# EthernetPHY.net
KiCad netlist of a schematic drawn in Altium Designer
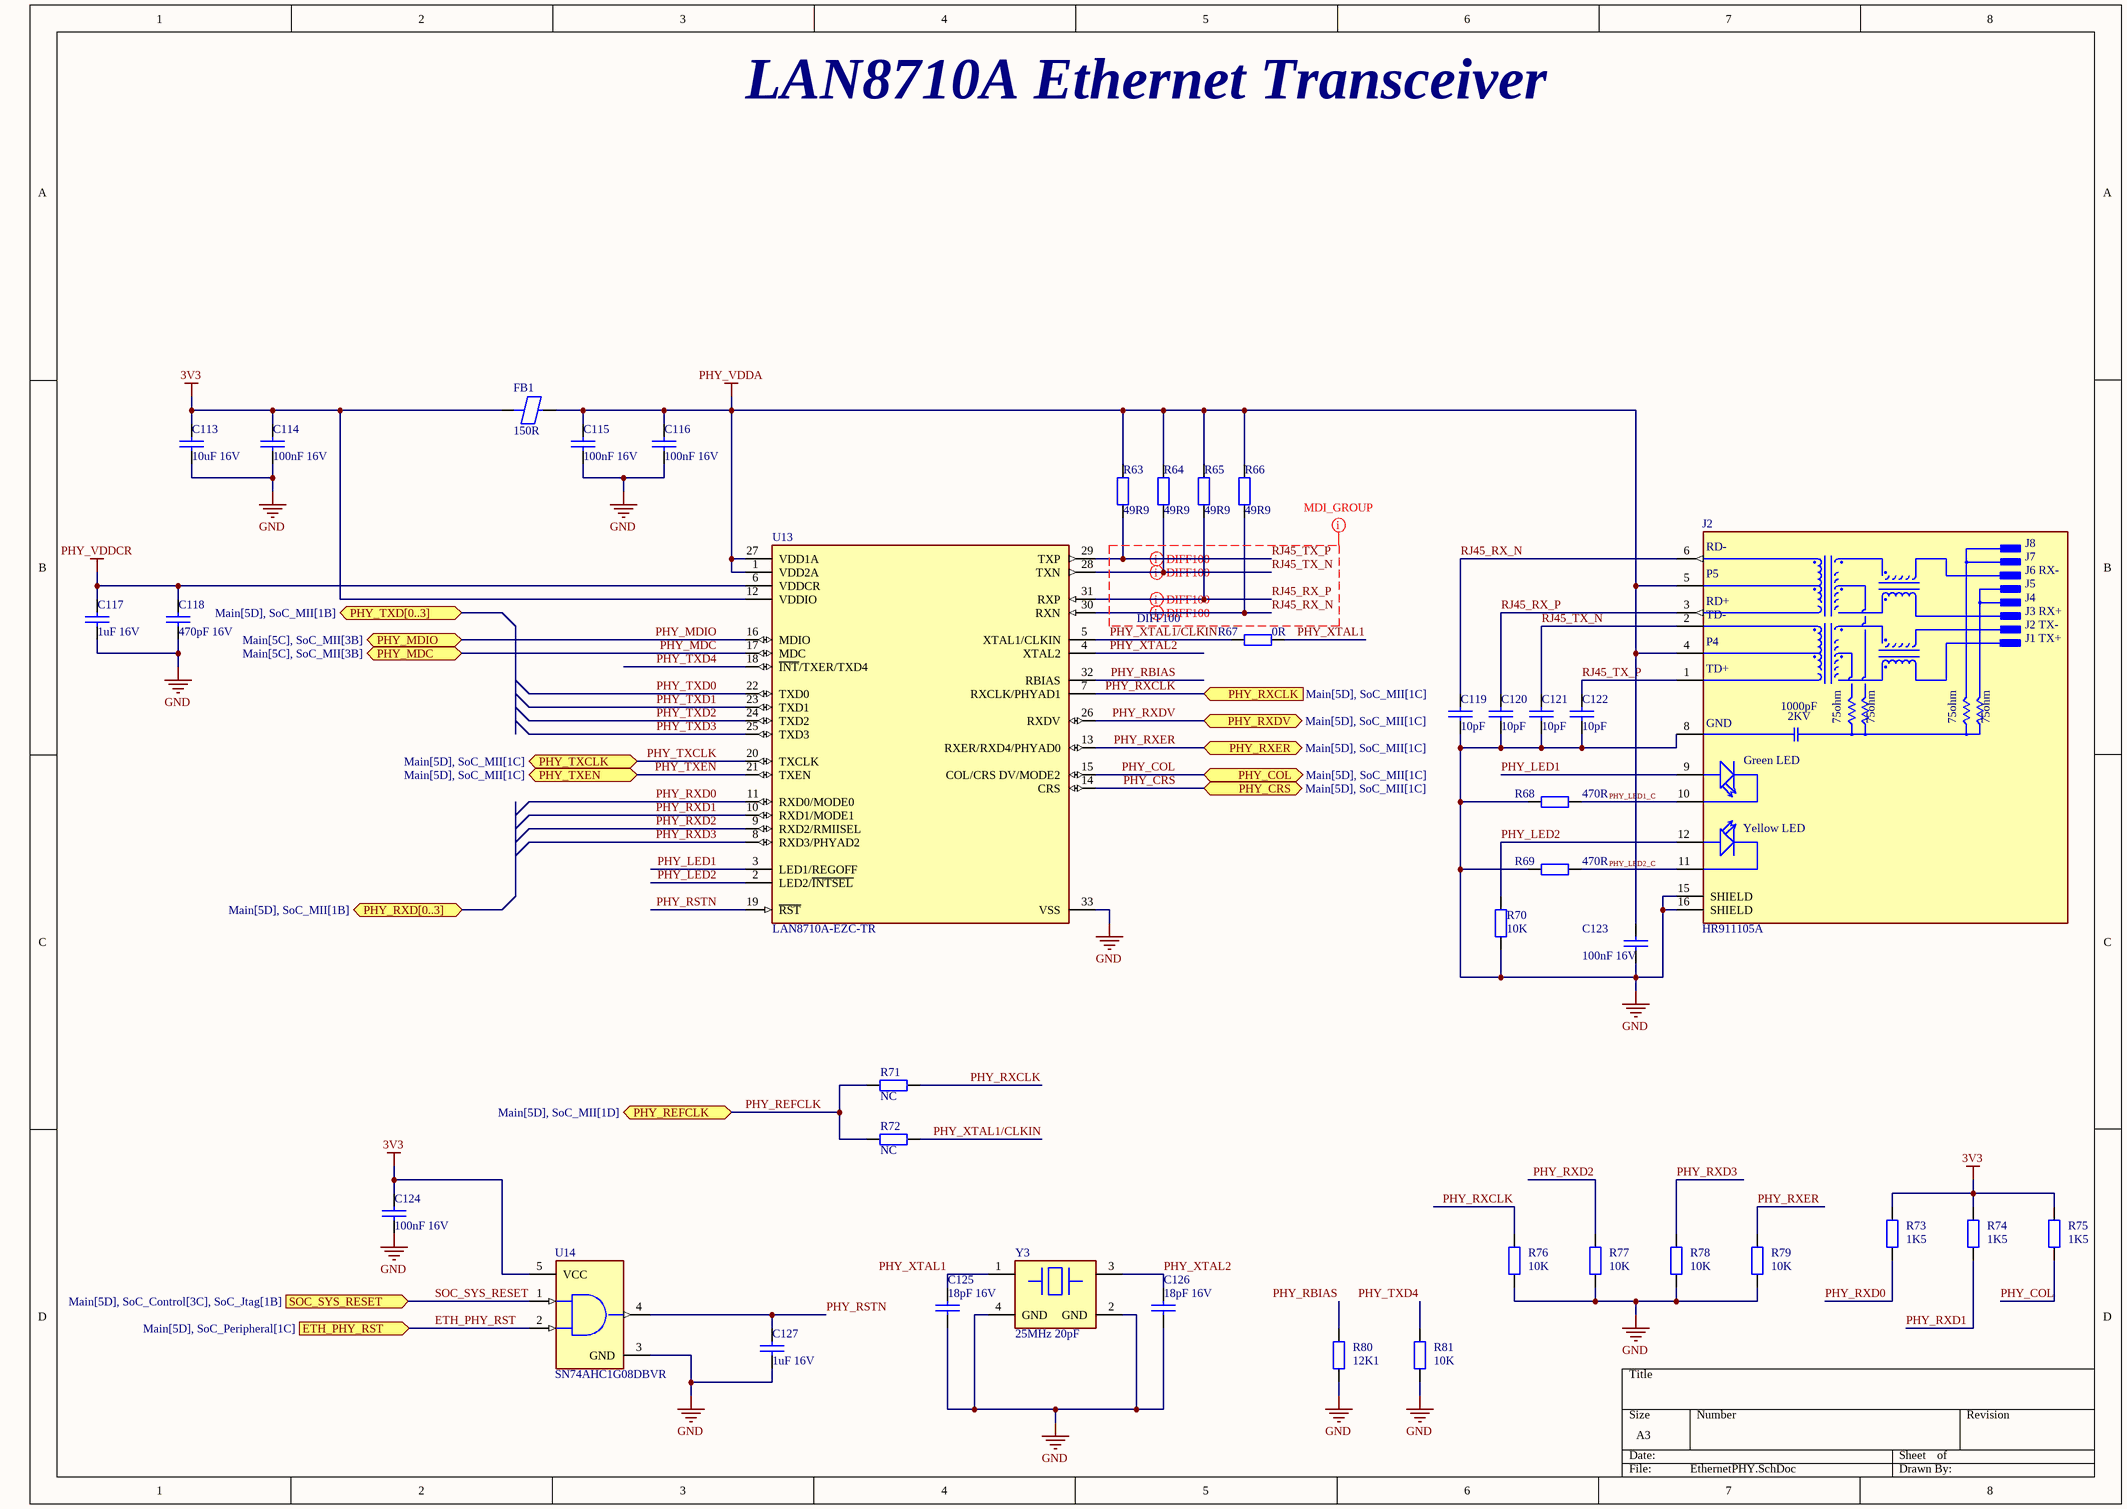
[diagram p0: EthernetPHY.SchDoc]

(export (version "E")
  (design (tool "Eeschema 10.0.6"))
  (components
    (comp (ref "C113")
      (value "10uF 16V")
      (footprint "C_0603")
      (description "Capacitor 0603 SMD")
      (libsource (lib "tor1kkLib") (part "C_0603"))
    )
    (comp (ref "C114")
      (value "100nF 16V")
      (footprint "C_0402")
      (description "Capacitor 0402 SMD")
      (libsource (lib "tor1kkLib") (part "C_0402"))
    )
    (comp (ref "C115")
      (value "100nF 16V")
      (footprint "C_0402")
      (description "Capacitor 0402 SMD")
      (libsource (lib "tor1kkLib") (part "C_0402"))
    )
    (comp (ref "C116")
      (value "100nF 16V")
      (footprint "C_0402")
      (description "Capacitor 0402 SMD")
      (libsource (lib "tor1kkLib") (part "C_0402"))
    )
    (comp (ref "C117")
      (value "1uF 16V")
      (footprint "C_0603")
      (description "Capacitor 0603 SMD")
      (libsource (lib "tor1kkLib") (part "C_0603"))
    )
    (comp (ref "C118")
      (value "470pF 16V")
      (footprint "C_0402")
      (description "Capacitor 0402 SMD")
      (libsource (lib "tor1kkLib") (part "C_0402"))
    )
    (comp (ref "C119")
      (value "10pF")
      (footprint "C_0402")
      (description "Capacitor 0402 SMD")
      (libsource (lib "tor1kkLib") (part "C_0402"))
    )
    (comp (ref "C120")
      (value "10pF")
      (footprint "C_0402")
      (description "Capacitor 0402 SMD")
      (libsource (lib "tor1kkLib") (part "C_0402"))
    )
    (comp (ref "C121")
      (value "10pF")
      (footprint "C_0402")
      (description "Capacitor 0402 SMD")
      (libsource (lib "tor1kkLib") (part "C_0402"))
    )
    (comp (ref "C122")
      (value "10pF")
      (footprint "C_0402")
      (description "Capacitor 0402 SMD")
      (libsource (lib "tor1kkLib") (part "C_0402"))
    )
    (comp (ref "C123")
      (value "100nF 16V")
      (footprint "C_0402")
      (description "Capacitor 0402 SMD")
      (libsource (lib "tor1kkLib") (part "C_0402"))
    )
    (comp (ref "C124")
      (value "100nF 16V")
      (footprint "C_0402")
      (description "Capacitor 0402 SMD")
      (libsource (lib "tor1kkLib") (part "C_0402"))
    )
    (comp (ref "C125")
      (value "18pF 16V")
      (footprint "C_0402")
      (description "Capacitor 0402 SMD")
      (libsource (lib "tor1kkLib") (part "C_0402"))
    )
    (comp (ref "C126")
      (value "18pF 16V")
      (footprint "C_0402")
      (description "Capacitor 0402 SMD")
      (libsource (lib "tor1kkLib") (part "C_0402"))
    )
    (comp (ref "C127")
      (value "1uF 16V")
      (footprint "C_0603")
      (description "Capacitor 0603 SMD")
      (libsource (lib "tor1kkLib") (part "C_0603"))
    )
    (comp (ref "FB1")
      (value "150R")
      (footprint "FB_0603")
      (description "Ferrite Beads 0603 SMD")
      (libsource (lib "tor1kkLib") (part "FB_0603"))
    )
    (comp (ref "J2")
      (value "HR911105A")
      (footprint "HR911105A")
      (description "RJ45Receptacle 1 WithLED Plugin Ethernet Connectors / Modular Connectors (RJ45 RJ11) ROHS")
      (libsource (lib "tor1kkLib") (part "HR911105A"))
    )
    (comp (ref "R63")
      (value "49R9")
      (footprint "R_0402")
      (description "Resistor 0402 SMD")
      (libsource (lib "") (part "R_0402_1"))
    )
    (comp (ref "R64")
      (value "49R9")
      (footprint "R_0402")
      (description "Resistor 0402 SMD")
      (libsource (lib "") (part "R_0402_1"))
    )
    (comp (ref "R65")
      (value "49R9")
      (footprint "R_0402")
      (description "Resistor 0402 SMD")
      (libsource (lib "") (part "R_0402_1"))
    )
    (comp (ref "R66")
      (value "49R9")
      (footprint "R_0402")
      (description "Resistor 0402 SMD")
      (libsource (lib "") (part "R_0402_1"))
    )
    (comp (ref "R67")
      (value "0R")
      (footprint "R_0402")
      (description "Resistor 0402 SMD")
      (libsource (lib "tor1kkLib") (part "R_0402"))
    )
    (comp (ref "R68")
      (value "470R")
      (footprint "R_0402")
      (description "Resistor 0402 SMD")
      (libsource (lib "tor1kkLib") (part "R_0402"))
    )
    (comp (ref "R69")
      (value "470R")
      (footprint "R_0402")
      (description "Resistor 0402 SMD")
      (libsource (lib "tor1kkLib") (part "R_0402"))
    )
    (comp (ref "R70")
      (value "10K")
      (footprint "R_0402")
      (description "Resistor 0402 SMD")
      (libsource (lib "") (part "R_0402_1"))
    )
    (comp (ref "R71")
      (value "NC")
      (footprint "R_0402")
      (description "Resistor 0402 SMD")
      (libsource (lib "") (part "R_0402_2"))
    )
    (comp (ref "R72")
      (value "NC")
      (footprint "R_0402")
      (description "Resistor 0402 SMD")
      (libsource (lib "") (part "R_0402_2"))
    )
    (comp (ref "R73")
      (value "1K5")
      (footprint "R_0402")
      (description "Resistor 0402 SMD")
      (libsource (lib "") (part "R_0402_1"))
    )
    (comp (ref "R74")
      (value "1K5")
      (footprint "R_0402")
      (description "Resistor 0402 SMD")
      (libsource (lib "") (part "R_0402_1"))
    )
    (comp (ref "R75")
      (value "1K5")
      (footprint "R_0402")
      (description "Resistor 0402 SMD")
      (libsource (lib "") (part "R_0402_1"))
    )
    (comp (ref "R76")
      (value "10K")
      (footprint "R_0402")
      (description "Resistor 0402 SMD")
      (libsource (lib "") (part "R_0402_1"))
    )
    (comp (ref "R77")
      (value "10K")
      (footprint "R_0402")
      (description "Resistor 0402 SMD")
      (libsource (lib "") (part "R_0402_1"))
    )
    (comp (ref "R78")
      (value "10K")
      (footprint "R_0402")
      (description "Resistor 0402 SMD")
      (libsource (lib "") (part "R_0402_1"))
    )
    (comp (ref "R79")
      (value "10K")
      (footprint "R_0402")
      (description "Resistor 0402 SMD")
      (libsource (lib "") (part "R_0402_1"))
    )
    (comp (ref "R80")
      (value "12K1")
      (footprint "R_0402")
      (description "Resistor 0402 SMD")
      (libsource (lib "") (part "R_0402_1"))
    )
    (comp (ref "R81")
      (value "10K")
      (footprint "R_0402")
      (description "Resistor 0402 SMD")
      (libsource (lib "") (part "R_0402_1"))
    )
    (comp (ref "U13")
      (value "LAN8710A-EZC-TR")
      (footprint "FP-LAN8710A-EZC-TR-MFG")
      (description "IC TRANSCEIVER FULL 4/4 32QFN")
      (libsource (lib "Altium Content Vault") (part "4194d6450c02c244e8cdb1b30fa00ec"))
    )
    (comp (ref "U14")
      (value "SN74AHC1G08DBVR")
      (footprint "FP-DBV0005A-MFG")
      (description "IC GATE AND 1CH 2-INP SOT23-5")
      (fields
        (field (name "MANUFACTURER") "Texas Instruments")
        (field (name "OCTOPART") "https://octopart.com/sn74ahc1g08dbvr-texas+instruments-464404")
      )
      (libsource (lib "Altium Content Vault") (part "7d5472fad8fac2169e6b8dda8b756c7"))
    )
    (comp (ref "Y3")
      (value "25MHz 20pF")
      (footprint "CRYSTAL_SMD3225-4P")
      (description "25MHz Surface Mount Crystal 20pF ±10ppm ±20ppm SMD3225-4P Crystals ROHS")
      (fields
        (field (name "MANUFACTURER") "YXC Crystal Oscillators")
        (field (name "MANUFACTURER PART NUMBER") "X322525MSB4SI")
      )
      (libsource (lib "tor1kkLib") (part "X322525MSB4SI"))
    )
  )
  (nets
    (net (code "1") (name "/ETH_PHY_RST") (class "Default")
      (node (ref "U14") (pin "2") (pinfunction "B_2") (pintype "input"))
    )
    (net (code "2") (name "/PHY_COL") (class "Default")
      (node (ref "R75") (pin "1") (pintype "passive"))
      (node (ref "U13") (pin "15") (pinfunction "COL/CRS_DV/MODE2_15") (pintype "bidirectional"))
    )
    (net (code "3") (name "/PHY_CRS") (class "Default")
      (node (ref "U13") (pin "14") (pinfunction "CRS_14") (pintype "bidirectional"))
    )
    (net (code "4") (name "/PHY_LED1") (class "Default")
      (node (ref "J2") (pin "9") (pinfunction "GA_9") (pintype "passive"))
      (node (ref "U13") (pin "3") (pinfunction "LED1/REGOFF_3") (pintype "passive"))
    )
    (net (code "5") (name "/PHY_LED1_C") (class "Default")
      (node (ref "J2") (pin "10") (pinfunction "GC_10") (pintype "passive"))
      (node (ref "R68") (pin "2") (pintype "passive"))
    )
    (net (code "6") (name "/PHY_LED2") (class "Default")
      (node (ref "J2") (pin "12") (pinfunction "YA_12") (pintype "passive"))
      (node (ref "R70") (pin "2") (pintype "passive"))
      (node (ref "U13") (pin "2") (pinfunction "LED2/~{INTSEL}_2") (pintype "passive"))
    )
    (net (code "7") (name "/PHY_LED2_C") (class "Default")
      (node (ref "J2") (pin "11") (pinfunction "YC_11") (pintype "passive"))
      (node (ref "R69") (pin "2") (pintype "passive"))
    )
    (net (code "8") (name "/PHY_MDC") (class "Default")
      (node (ref "U13") (pin "17") (pinfunction "MDC_17") (pintype "bidirectional"))
    )
    (net (code "9") (name "/PHY_MDIO") (class "Default")
      (node (ref "U13") (pin "16") (pinfunction "MDIO_16") (pintype "bidirectional"))
    )
    (net (code "10") (name "/PHY_RBIAS") (class "Default")
      (node (ref "R80") (pin "2") (pintype "passive"))
      (node (ref "U13") (pin "32") (pinfunction "RBIAS_32") (pintype "passive"))
    )
    (net (code "11") (name "/PHY_REFCLK") (class "Default")
      (node (ref "R71") (pin "2") (pintype "passive"))
      (node (ref "R72") (pin "2") (pintype "passive"))
    )
    (net (code "12") (name "/PHY_RSTN") (class "Default")
      (node (ref "C127") (pin "1") (pintype "passive"))
      (node (ref "U13") (pin "19") (pinfunction "~{RST}_19") (pintype "input"))
      (node (ref "U14") (pin "4") (pinfunction "Y_4") (pintype "output"))
    )
    (net (code "13") (name "/PHY_RXCLK") (class "Default")
      (node (ref "R71") (pin "1") (pintype "passive"))
      (node (ref "R76") (pin "2") (pintype "passive"))
      (node (ref "U13") (pin "7") (pinfunction "RXCLK/PHYAD1_7") (pintype "passive"))
    )
    (net (code "14") (name "/PHY_RXD0") (class "Default")
      (node (ref "R73") (pin "1") (pintype "passive"))
      (node (ref "U13") (pin "11") (pinfunction "RXD0/MODE0_11") (pintype "bidirectional"))
    )
    (net (code "15") (name "/PHY_RXD1") (class "Default")
      (node (ref "R74") (pin "1") (pintype "passive"))
      (node (ref "U13") (pin "10") (pinfunction "RXD1/MODE1_10") (pintype "bidirectional"))
    )
    (net (code "16") (name "/PHY_RXD2") (class "Default")
      (node (ref "R77") (pin "2") (pintype "passive"))
      (node (ref "U13") (pin "9") (pinfunction "RXD2/RMIISEL_9") (pintype "bidirectional"))
    )
    (net (code "17") (name "/PHY_RXD3") (class "Default")
      (node (ref "R78") (pin "2") (pintype "passive"))
      (node (ref "U13") (pin "8") (pinfunction "RXD3/PHYAD2_8") (pintype "bidirectional"))
    )
    (net (code "18") (name "/PHY_RXDV") (class "Default")
      (node (ref "U13") (pin "26") (pinfunction "RXDV_26") (pintype "bidirectional"))
    )
    (net (code "20") (name "/PHY_RXER") (class "Default")
      (node (ref "R79") (pin "2") (pintype "passive"))
      (node (ref "U13") (pin "13") (pinfunction "RXER/RXD4/PHYAD0_13") (pintype "bidirectional"))
    )
    (net (code "21") (name "/PHY_TXCLK") (class "Default")
      (node (ref "U13") (pin "20") (pinfunction "TXCLK_20") (pintype "bidirectional"))
    )
    (net (code "22") (name "/PHY_TXD0") (class "Default")
      (node (ref "U13") (pin "22") (pinfunction "TXD0_22") (pintype "bidirectional"))
    )
    (net (code "23") (name "/PHY_TXD1") (class "Default")
      (node (ref "U13") (pin "23") (pinfunction "TXD1_23") (pintype "bidirectional"))
    )
    (net (code "24") (name "/PHY_TXD2") (class "Default")
      (node (ref "U13") (pin "24") (pinfunction "TXD2_24") (pintype "bidirectional"))
    )
    (net (code "25") (name "/PHY_TXD3") (class "Default")
      (node (ref "U13") (pin "25") (pinfunction "TXD3_25") (pintype "bidirectional"))
    )
    (net (code "26") (name "/PHY_TXD4") (class "Default")
      (node (ref "R81") (pin "2") (pintype "passive"))
      (node (ref "U13") (pin "18") (pinfunction "~{INT}/TXER/TXD4_18") (pintype "bidirectional"))
    )
    (net (code "28") (name "/PHY_TXEN") (class "Default")
      (node (ref "U13") (pin "21") (pinfunction "TXEN_21") (pintype "bidirectional"))
    )
    (net (code "29") (name "/PHY_XTAL1") (class "Default")
      (node (ref "C125") (pin "2") (pintype "passive"))
      (node (ref "R67") (pin "2") (pintype "passive"))
      (node (ref "Y3") (pin "1") (pinfunction "CRYSTAL_1_1") (pintype "passive"))
    )
    (net (code "30") (name "/PHY_XTAL1{slash}CLKIN") (class "Default")
      (node (ref "R67") (pin "1") (pintype "passive"))
      (node (ref "R72") (pin "1") (pintype "passive"))
      (node (ref "U13") (pin "5") (pinfunction "XTAL1/CLKIN_5") (pintype "passive"))
    )
    (net (code "31") (name "/PHY_XTAL2") (class "Default")
      (node (ref "C126") (pin "2") (pintype "passive"))
      (node (ref "U13") (pin "4") (pinfunction "XTAL2_4") (pintype "passive"))
      (node (ref "Y3") (pin "3") (pinfunction "CRYSTAL_2_3") (pintype "passive"))
    )
    (net (code "32") (name "/RJ45_RX_N") (class "Default")
      (node (ref "C119") (pin "1") (pintype "passive"))
      (node (ref "J2") (pin "6") (pinfunction "RD-_6") (pintype "output"))
      (node (ref "R66") (pin "1") (pintype "passive"))
      (node (ref "U13") (pin "30") (pinfunction "RXN_30") (pintype "input"))
    )
    (net (code "33") (name "/RJ45_RX_P") (class "Default")
      (node (ref "C120") (pin "1") (pintype "passive"))
      (node (ref "J2") (pin "3") (pinfunction "RD+_3") (pintype "output"))
      (node (ref "R65") (pin "1") (pintype "passive"))
      (node (ref "U13") (pin "31") (pinfunction "RXP_31") (pintype "input"))
    )
    (net (code "34") (name "/RJ45_TX_N") (class "Default")
      (node (ref "C121") (pin "1") (pintype "passive"))
      (node (ref "J2") (pin "2") (pinfunction "TD-_2") (pintype "passive"))
      (node (ref "R64") (pin "1") (pintype "passive"))
      (node (ref "U13") (pin "28") (pinfunction "TXN_28") (pintype "output"))
    )
    (net (code "35") (name "/RJ45_TX_P") (class "Default")
      (node (ref "C122") (pin "1") (pintype "passive"))
      (node (ref "J2") (pin "1") (pinfunction "TD+_1") (pintype "passive"))
      (node (ref "R63") (pin "1") (pintype "passive"))
      (node (ref "U13") (pin "29") (pinfunction "TXP_29") (pintype "output"))
    )
    (net (code "36") (name "/SOC_SYS_RESET") (class "Default")
      (node (ref "U14") (pin "1") (pinfunction "A_1") (pintype "input"))
    )
    (net (code "37") (name "3V3") (class "Default")
      (node (ref "C113") (pin "1") (pintype "passive"))
      (node (ref "C114") (pin "1") (pintype "passive"))
      (node (ref "C124") (pin "1") (pintype "passive"))
      (node (ref "FB1") (pin "1") (pintype "passive"))
      (node (ref "R73") (pin "2") (pintype "passive"))
      (node (ref "R74") (pin "2") (pintype "passive"))
      (node (ref "R75") (pin "2") (pintype "passive"))
      (node (ref "U13") (pin "12") (pinfunction "VDDIO_12") (pintype "power_in"))
      (node (ref "U14") (pin "5") (pinfunction "VCC_5") (pintype "power_in"))
    )
    (net (code "38") (name "GND") (class "Default")
      (node (ref "C113") (pin "2") (pintype "passive"))
      (node (ref "C114") (pin "2") (pintype "passive"))
      (node (ref "C115") (pin "2") (pintype "passive"))
      (node (ref "C116") (pin "2") (pintype "passive"))
      (node (ref "C117") (pin "2") (pintype "passive"))
      (node (ref "C118") (pin "2") (pintype "passive"))
      (node (ref "C119") (pin "2") (pintype "passive"))
      (node (ref "C120") (pin "2") (pintype "passive"))
      (node (ref "C121") (pin "2") (pintype "passive"))
      (node (ref "C122") (pin "2") (pintype "passive"))
      (node (ref "C123") (pin "2") (pintype "passive"))
      (node (ref "C124") (pin "2") (pintype "passive"))
      (node (ref "C125") (pin "1") (pintype "passive"))
      (node (ref "C126") (pin "1") (pintype "passive"))
      (node (ref "C127") (pin "2") (pintype "passive"))
      (node (ref "J2") (pin "15") (pinfunction "SHIELD_15") (pintype "passive"))
      (node (ref "J2") (pin "16") (pinfunction "SHIELD_16") (pintype "passive"))
      (node (ref "J2") (pin "8") (pinfunction "GND_8") (pintype "power_in"))
      (node (ref "R68") (pin "1") (pintype "passive"))
      (node (ref "R69") (pin "1") (pintype "passive"))
      (node (ref "R70") (pin "1") (pintype "passive"))
      (node (ref "R76") (pin "1") (pintype "passive"))
      (node (ref "R77") (pin "1") (pintype "passive"))
      (node (ref "R78") (pin "1") (pintype "passive"))
      (node (ref "R79") (pin "1") (pintype "passive"))
      (node (ref "R80") (pin "1") (pintype "passive"))
      (node (ref "R81") (pin "1") (pintype "passive"))
      (node (ref "U13") (pin "33") (pinfunction "VSS_33") (pintype "power_in"))
      (node (ref "U14") (pin "3") (pinfunction "GND_3") (pintype "power_in"))
      (node (ref "Y3") (pin "2") (pinfunction "GND_2") (pintype "passive"))
      (node (ref "Y3") (pin "4") (pinfunction "GND_4") (pintype "passive"))
    )
    (net (code "39") (name "PHY_VDDA") (class "Default")
      (node (ref "C115") (pin "1") (pintype "passive"))
      (node (ref "C116") (pin "1") (pintype "passive"))
      (node (ref "C123") (pin "1") (pintype "passive"))
      (node (ref "FB1") (pin "2") (pintype "passive"))
      (node (ref "J2") (pin "4") (pinfunction "P4_4") (pintype "passive"))
      (node (ref "J2") (pin "5") (pinfunction "P5_5") (pintype "passive"))
      (node (ref "R63") (pin "2") (pintype "passive"))
      (node (ref "R64") (pin "2") (pintype "passive"))
      (node (ref "R65") (pin "2") (pintype "passive"))
      (node (ref "R66") (pin "2") (pintype "passive"))
      (node (ref "U13") (pin "1") (pinfunction "VDD2A_1") (pintype "power_in"))
      (node (ref "U13") (pin "27") (pinfunction "VDD1A_27") (pintype "power_in"))
    )
    (net (code "40") (name "PHY_VDDCR") (class "Default")
      (node (ref "C117") (pin "1") (pintype "passive"))
      (node (ref "C118") (pin "1") (pintype "passive"))
      (node (ref "U13") (pin "6") (pinfunction "VDDCR_6") (pintype "power_in"))
    )
  )
)
